# phillip.net
KiCad netlist of a schematic drawn in EAGLE
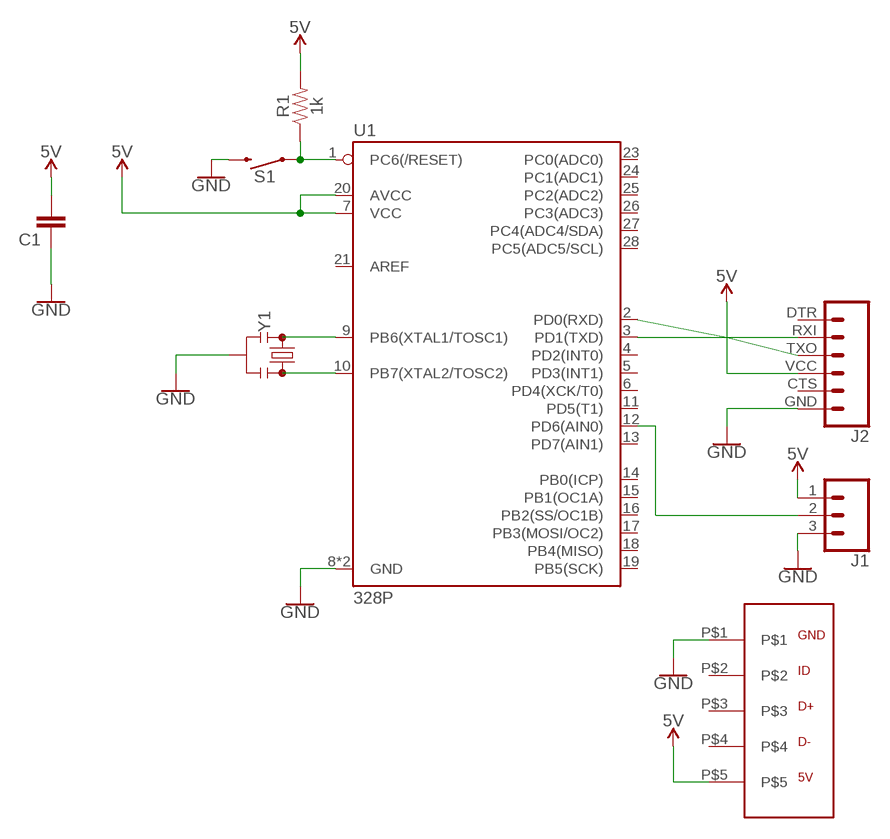
[diagram p0: schematic, sheet 1]

(export (version "E")
  (design (tool "Eeschema 10.0.6"))
  (components
    (comp (ref "C1")
      (value "C10/4")
      (footprint "eagle-import:C10B4")
      (libsource (lib "eagle-import") (part "C10/4"))
    )
    (comp (ref "J1")
      (value "CONN_03POLAR")
      (footprint "eagle-import:MOLEX-1X3")
      (libsource (lib "eagle-import") (part "CONN_03POLAR"))
    )
    (comp (ref "J2")
      (value "6_PIN_SERIAL_CABLEPTH")
      (footprint "eagle-import:FTDI_BASIC")
      (libsource (lib "eagle-import") (part "6_PIN_SERIAL_CABLEPTH"))
    )
    (comp (ref "R1")
      (value "1k")
      (footprint "eagle-import:AXIAL-0.3")
      (libsource (lib "eagle-import") (part "1KOHM-HORIZ-1/4W-1%"))
    )
    (comp (ref "S1")
      (value "MOMENTARY-SWITCH-SPST-PTH-6.0MM")
      (footprint "eagle-import:TACTILE_SWITCH_PTH_6.0MM")
      (libsource (lib "eagle-import") (part "MOMENTARY-SWITCH-SPST-PTH-6.0MM"))
    )
    (comp (ref "U$1")
      (value "USB_CON1")
      (footprint "eagle-import:USB-CON")
      (libsource (lib "eagle-import") (part "USB_CON1"))
    )
    (comp (ref "U1")
      (value "328P")
      (footprint "eagle-import:DIP28")
      (libsource (lib "eagle-import") (part "ATMEGA328P_PDIP"))
    )
    (comp (ref "Y1")
      (value "RESONATORPTH-7.6X3.8")
      (footprint "eagle-import:RESONATOR-PTH-7.6X3.8")
      (libsource (lib "eagle-import") (part "RESONATORPTH-7.6X3.8"))
    )
  )
  (nets
    (net (code "1") (name "5V") (class "Default")
      (node (ref "C1") (pin "2") (pinfunction "2_2") (pintype "passive"))
      (node (ref "J1") (pin "1") (pinfunction "1_1") (pintype "passive"))
      (node (ref "J2") (pin "VCC") (pinfunction "4_VCC") (pintype "passive"))
      (node (ref "R1") (pin "P$2") (pinfunction "2_P$2") (pintype "passive"))
      (node (ref "U$1") (pin "P$5") (pinfunction "P$5_P$5") (pintype "bidirectional"))
      (node (ref "U1") (pin "20") (pinfunction "AVCC_20") (pintype "bidirectional"))
      (node (ref "U1") (pin "7") (pinfunction "VCC_7") (pintype "bidirectional"))
    )
    (net (code "2") (name "GND") (class "Default")
      (node (ref "C1") (pin "1") (pinfunction "1_1") (pintype "passive"))
      (node (ref "J1") (pin "3") (pinfunction "3_3") (pintype "passive"))
      (node (ref "J2") (pin "GND") (pinfunction "6_GND") (pintype "passive"))
      (node (ref "S1") (pin "3") (pinfunction "2_3") (pintype "passive"))
      (node (ref "U$1") (pin "P$1") (pinfunction "P$1_P$1") (pintype "bidirectional"))
      (node (ref "U1") (pin "22") (pinfunction "GND_22") (pintype "bidirectional"))
      (node (ref "U1") (pin "8") (pinfunction "GND_8") (pintype "bidirectional"))
      (node (ref "Y1") (pin "2") (pinfunction "2_2") (pintype "passive"))
    )
    (net (code "3") (name "Net-(J2-2)") (class "Default")
      (node (ref "J2") (pin "RXI") (pinfunction "2_RXI") (pintype "passive"))
      (node (ref "U1") (pin "3") (pinfunction "PD1(TXD)_3") (pintype "bidirectional"))
    )
    (net (code "4") (name "Net-(J2-3)") (class "Default")
      (node (ref "J2") (pin "TXO") (pinfunction "3_TXO") (pintype "passive"))
      (node (ref "U1") (pin "2") (pinfunction "PD0(RXD)_2") (pintype "bidirectional"))
    )
    (net (code "5") (name "Net-(R1-1)") (class "Default")
      (node (ref "R1") (pin "P$1") (pinfunction "1_P$1") (pintype "passive"))
      (node (ref "S1") (pin "1") (pinfunction "1_1") (pintype "passive"))
      (node (ref "U1") (pin "1") (pinfunction "PC6(/RESET)_1") (pintype "bidirectional"))
    )
    (net (code "6") (name "Net-(U1-PB6(XTAL1{slash}TOSC1))") (class "Default")
      (node (ref "U1") (pin "9") (pinfunction "PB6(XTAL1/TOSC1)_9") (pintype "bidirectional"))
      (node (ref "Y1") (pin "1") (pinfunction "1_1") (pintype "passive"))
    )
    (net (code "7") (name "Net-(U1-PB7(XTAL2{slash}TOSC2))") (class "Default")
      (node (ref "U1") (pin "10") (pinfunction "PB7(XTAL2/TOSC2)_10") (pintype "bidirectional"))
      (node (ref "Y1") (pin "3") (pinfunction "3_3") (pintype "passive"))
    )
    (net (code "8") (name "Net-(U1-PD6(AIN0))") (class "Default")
      (node (ref "J1") (pin "2") (pinfunction "2_2") (pintype "passive"))
      (node (ref "U1") (pin "12") (pinfunction "PD6(AIN0)_12") (pintype "bidirectional"))
    )
    (net (code "9") (name "unconnected-(J2-1-PadDTR)") (class "Default")
      (node (ref "J2") (pin "DTR") (pinfunction "1_DTR") (pintype "passive"))
    )
    (net (code "10") (name "unconnected-(J2-5-PadCTS)") (class "Default")
      (node (ref "J2") (pin "CTS") (pinfunction "5_CTS") (pintype "passive"))
    )
    (net (code "11") (name "unconnected-(U$1-PadP$2)") (class "Default")
      (node (ref "U$1") (pin "P$2") (pinfunction "P$2_P$2") (pintype "bidirectional"))
    )
    (net (code "12") (name "unconnected-(U$1-PadP$3)") (class "Default")
      (node (ref "U$1") (pin "P$3") (pinfunction "P$3_P$3") (pintype "bidirectional"))
    )
    (net (code "13") (name "unconnected-(U$1-PadP$4)") (class "Default")
      (node (ref "U$1") (pin "P$4") (pinfunction "P$4_P$4") (pintype "bidirectional"))
    )
    (net (code "14") (name "unconnected-(U1-AREF-Pad21)") (class "Default")
      (node (ref "U1") (pin "21") (pinfunction "AREF_21") (pintype "bidirectional"))
    )
    (net (code "15") (name "unconnected-(U1-PB0(ICP)-Pad14)") (class "Default")
      (node (ref "U1") (pin "14") (pinfunction "PB0(ICP)_14") (pintype "bidirectional"))
    )
    (net (code "16") (name "unconnected-(U1-PB1(OC1A)-Pad15)") (class "Default")
      (node (ref "U1") (pin "15") (pinfunction "PB1(OC1A)_15") (pintype "bidirectional"))
    )
    (net (code "17") (name "unconnected-(U1-PB2(SS{slash}OC1B)-Pad16)") (class "Default")
      (node (ref "U1") (pin "16") (pinfunction "PB2(SS/OC1B)_16") (pintype "bidirectional"))
    )
    (net (code "18") (name "unconnected-(U1-PB3(MOSI{slash}OC2)-Pad17)") (class "Default")
      (node (ref "U1") (pin "17") (pinfunction "PB3(MOSI/OC2)_17") (pintype "bidirectional"))
    )
    (net (code "19") (name "unconnected-(U1-PB4(MISO)-Pad18)") (class "Default")
      (node (ref "U1") (pin "18") (pinfunction "PB4(MISO)_18") (pintype "bidirectional"))
    )
    (net (code "20") (name "unconnected-(U1-PB5(SCK)-Pad19)") (class "Default")
      (node (ref "U1") (pin "19") (pinfunction "PB5(SCK)_19") (pintype "bidirectional"))
    )
    (net (code "21") (name "unconnected-(U1-PC0(ADC0)-Pad23)") (class "Default")
      (node (ref "U1") (pin "23") (pinfunction "PC0(ADC0)_23") (pintype "bidirectional"))
    )
    (net (code "22") (name "unconnected-(U1-PC1(ADC1)-Pad24)") (class "Default")
      (node (ref "U1") (pin "24") (pinfunction "PC1(ADC1)_24") (pintype "bidirectional"))
    )
    (net (code "23") (name "unconnected-(U1-PC2(ADC2)-Pad25)") (class "Default")
      (node (ref "U1") (pin "25") (pinfunction "PC2(ADC2)_25") (pintype "bidirectional"))
    )
    (net (code "24") (name "unconnected-(U1-PC3(ADC3)-Pad26)") (class "Default")
      (node (ref "U1") (pin "26") (pinfunction "PC3(ADC3)_26") (pintype "bidirectional"))
    )
    (net (code "25") (name "unconnected-(U1-PC4(ADC4{slash}SDA)-Pad27)") (class "Default")
      (node (ref "U1") (pin "27") (pinfunction "PC4(ADC4/SDA)_27") (pintype "bidirectional"))
    )
    (net (code "26") (name "unconnected-(U1-PC5(ADC5{slash}SCL)-Pad28)") (class "Default")
      (node (ref "U1") (pin "28") (pinfunction "PC5(ADC5/SCL)_28") (pintype "bidirectional"))
    )
    (net (code "27") (name "unconnected-(U1-PD2(INT0)-Pad4)") (class "Default")
      (node (ref "U1") (pin "4") (pinfunction "PD2(INT0)_4") (pintype "bidirectional"))
    )
    (net (code "28") (name "unconnected-(U1-PD3(INT1)-Pad5)") (class "Default")
      (node (ref "U1") (pin "5") (pinfunction "PD3(INT1)_5") (pintype "bidirectional"))
    )
    (net (code "29") (name "unconnected-(U1-PD4(XCK{slash}T0)-Pad6)") (class "Default")
      (node (ref "U1") (pin "6") (pinfunction "PD4(XCK/T0)_6") (pintype "bidirectional"))
    )
    (net (code "30") (name "unconnected-(U1-PD5(T1)-Pad11)") (class "Default")
      (node (ref "U1") (pin "11") (pinfunction "PD5(T1)_11") (pintype "bidirectional"))
    )
    (net (code "31") (name "unconnected-(U1-PD7(AIN1)-Pad13)") (class "Default")
      (node (ref "U1") (pin "13") (pinfunction "PD7(AIN1)_13") (pintype "bidirectional"))
    )
  )
)
